# MAIN.net
KiCad netlist of a schematic drawn in Altium Designer
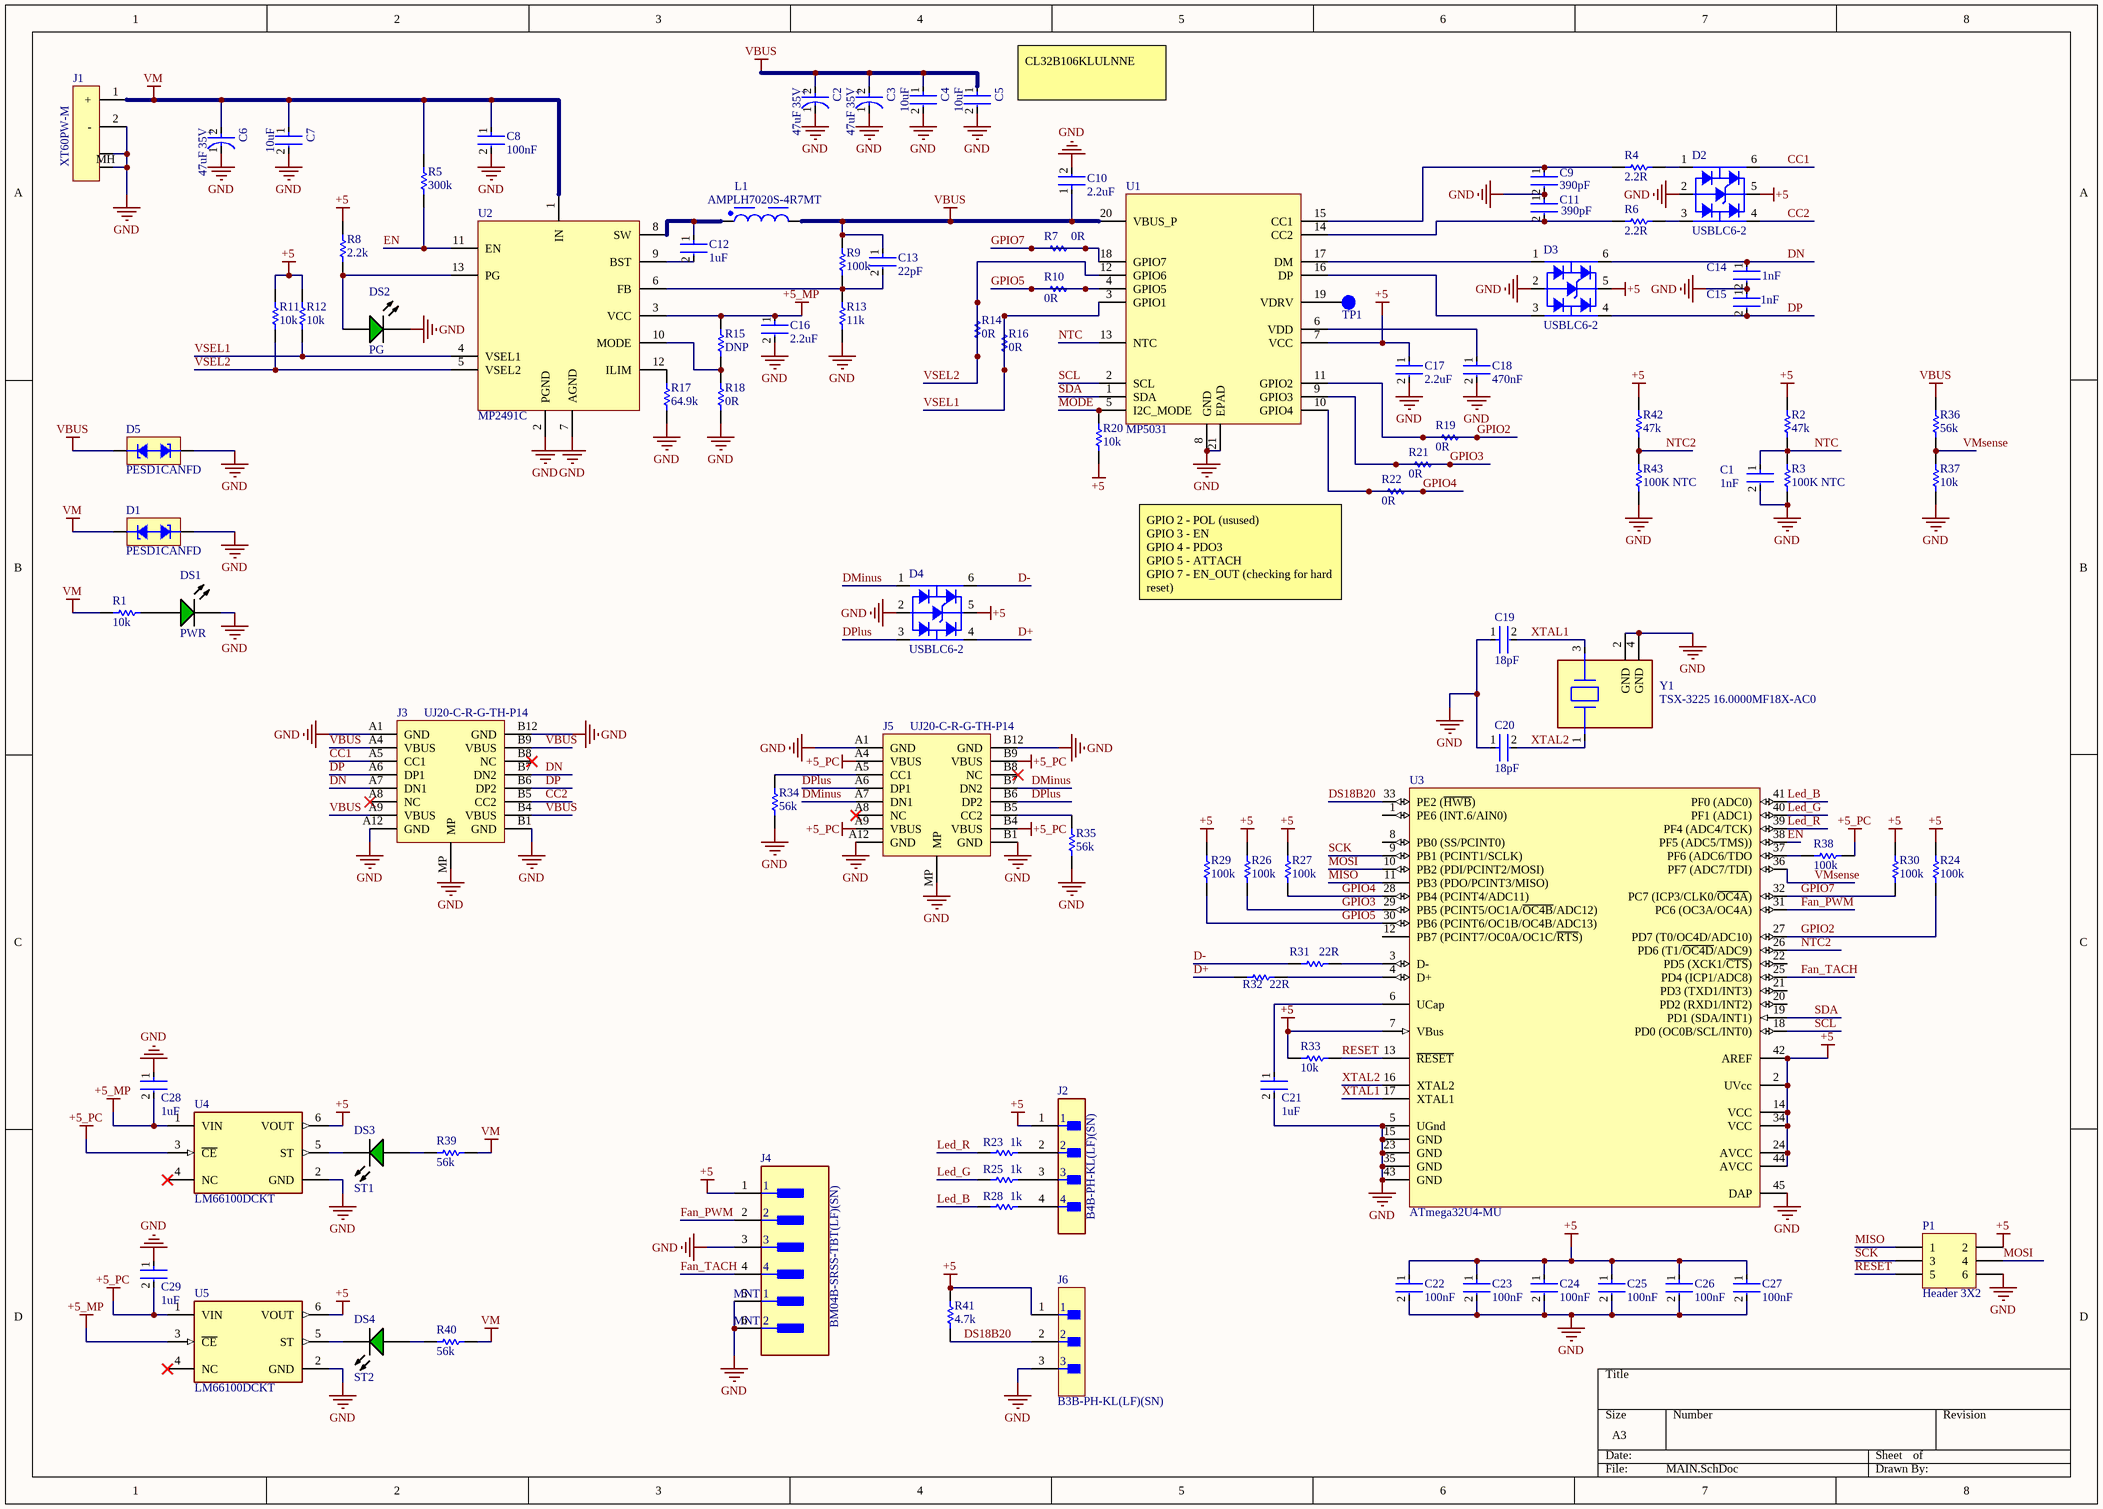
[diagram p0: MAIN.SchDoc]

(export (version "E")
  (design (tool "Eeschema 10.0.6"))
  (components
    (comp (ref "C1")
      (value "1nF")
      (footprint "FP-0603-L_1_6_0_15-W_0_81-IPC_B")
      (description "General Purpose Ceramic Capacitor, 0603, 1nF, 10%, X7R, 15%, 50V")
      (fields (field (name "VOLTAGE") "50V") (field (name "TOLERANCE") "10%"))
      (libsource (lib "Altium Content Vault") (part "02cd4be3c70576c341d710602a673aa"))
    )
    (comp (ref "C2")
      (value "47uF 35V")
      (footprint "FP-T491X476K035AT-MFG")
      (description "CAP TANT 47UF 10% 35V 2917")
      (fields (field (name "TOLERANCE") "10%") (field (name "VOLTAGE") "35V"))
      (libsource (lib "Altium Content Vault") (part "203bc49f2ac43e59fd269a8c329ed05"))
    )
    (comp (ref "C3")
      (value "47uF 35V")
      (footprint "FP-T491X476K035AT-MFG")
      (description "CAP TANT 47UF 10% 35V 2917")
      (fields (field (name "TOLERANCE") "10%") (field (name "VOLTAGE") "35V"))
      (libsource (lib "Altium Content Vault") (part "203bc49f2ac43e59fd269a8c329ed05"))
    )
    (comp (ref "C4")
      (value "10uF")
      (footprint "FP-C1210C106M6PACTU-MFG")
      (description "CAP CER 10UF 35V X5R 1210")
      (fields (field (name "VOLTAGE") "35V") (field (name "TOLERANCE") "20%"))
      (libsource (lib "Altium Content Vault") (part "02cd4be3c70576c341d710602a673aa"))
    )
    (comp (ref "C5")
      (value "10uF")
      (footprint "FP-C1210C106M6PACTU-MFG")
      (description "CAP CER 10UF 35V X5R 1210")
      (fields (field (name "VOLTAGE") "35V") (field (name "TOLERANCE") "20%"))
      (libsource (lib "Altium Content Vault") (part "02cd4be3c70576c341d710602a673aa"))
    )
    (comp (ref "C6")
      (value "47uF 35V")
      (footprint "FP-T491X476K035AT-MFG")
      (description "CAP TANT 47UF 10% 35V 2917")
      (fields (field (name "TOLERANCE") "10%") (field (name "VOLTAGE") "35V"))
      (libsource (lib "Altium Content Vault") (part "203bc49f2ac43e59fd269a8c329ed05"))
    )
    (comp (ref "C7")
      (value "10uF")
      (footprint "FP-C1210C106M6PACTU-MFG")
      (description "CAP CER 10UF 35V X5R 1210")
      (fields (field (name "VOLTAGE") "35V") (field (name "TOLERANCE") "20%"))
      (libsource (lib "Altium Content Vault") (part "02cd4be3c70576c341d710602a673aa"))
    )
    (comp (ref "C8")
      (value "100nF")
      (footprint "FP-0603-L_1_6_0_1-W_0_8_0-IPC_C")
      (description "None")
      (fields (field (name "TOLERANCE") "10%"))
      (libsource (lib "Altium Content Vault") (part "02cd4be3c70576c341d710602a673aa"))
    )
    (comp (ref "C9")
      (value "390pF")
      (footprint "FP-C0603C-CF-IPC_B")
      (description "CAP CER 390PF 50V C0G/NP0 0603")
      (fields
        (field (name "MANUFACTURER") "KEMET")
        (field (name "MANUFACTURER PART NUMBER") "C0603C391J5GACTU")
      )
      (libsource (lib "Altium Content Vault") (part "b4654b650e69147ec39a6b967a45e02"))
    )
    (comp (ref "C10")
      (value "2.2uF")
      (footprint "FP-GRM188-0_1-e0_2_0_5-IPC_B")
      (description "Chip Multilayer Ceramic Capacitors for General Purpose, 0603, 2.2uF, X7R, 15%, 10%, 10V")
      (fields (field (name "VOLTAGE") "10V") (field (name "TOLERANCE") "10%"))
      (libsource (lib "Altium Content Vault") (part "11868f565c42a9108669ba33697ecf6"))
    )
    (comp (ref "C11")
      (value "390pF")
      (footprint "FP-C0603C-CF-IPC_B")
      (description "CAP CER 390PF 50V C0G/NP0 0603")
      (fields
        (field (name "MANUFACTURER") "KEMET")
        (field (name "MANUFACTURER PART NUMBER") "C0603C391J5GACTU")
      )
      (libsource (lib "Altium Content Vault") (part "b4654b650e69147ec39a6b967a45e02"))
    )
    (comp (ref "C12")
      (value "1uF")
      (footprint "FP-0603-L_1_6_0_15-W_0_81-IPC_B")
      (description "General Purpose Ceramic Capacitor, 0603, 1uF, 10%, X5R, 15%, 16V")
      (fields (field (name "VOLTAGE") "16V") (field (name "TOLERANCE") "10%"))
      (libsource (lib "Altium Content Vault") (part "02cd4be3c70576c341d710602a673aa"))
    )
    (comp (ref "C13")
      (value "22pF")
      (footprint "FP-C0603C-CF-MFG")
      (description "Cap Ceramic 22pF 50V C0G 5% SMD 0603 125°C Paper T/R")
      (fields (field (name "MANUFACTURER PART NUMBER") "C0603C220J5GACTU") (field (name "TOLERANCE") "0.05"))
      (libsource (lib "Altium Content Vault") (part "b4654b650e69147ec39a6b967a45e02"))
    )
    (comp (ref "C14")
      (value "1nF")
      (footprint "FP-0603-L_1_6_0_15-W_0_81-IPC_B")
      (description "General Purpose Ceramic Capacitor, 0603, 1nF, 10%, X7R, 15%, 50V")
      (fields (field (name "VOLTAGE") "50V") (field (name "TOLERANCE") "10%"))
      (libsource (lib "Altium Content Vault") (part "02cd4be3c70576c341d710602a673aa"))
    )
    (comp (ref "C15")
      (value "1nF")
      (footprint "FP-0603-L_1_6_0_15-W_0_81-IPC_B")
      (description "General Purpose Ceramic Capacitor, 0603, 1nF, 10%, X7R, 15%, 50V")
      (fields (field (name "VOLTAGE") "50V") (field (name "TOLERANCE") "10%"))
      (libsource (lib "Altium Content Vault") (part "02cd4be3c70576c341d710602a673aa"))
    )
    (comp (ref "C16")
      (value "2.2uF")
      (footprint "FP-GRM188-0_1-e0_2_0_5-IPC_B")
      (description "Chip Multilayer Ceramic Capacitors for General Purpose, 0603, 2.2uF, X7R, 15%, 10%, 10V")
      (fields (field (name "VOLTAGE") "10V") (field (name "TOLERANCE") "10%"))
      (libsource (lib "Altium Content Vault") (part "11868f565c42a9108669ba33697ecf6"))
    )
    (comp (ref "C17")
      (value "2.2uF")
      (footprint "FP-GRM188-0_1-e0_2_0_5-IPC_B")
      (description "Chip Multilayer Ceramic Capacitors for General Purpose, 0603, 2.2uF, X7R, 15%, 10%, 10V")
      (fields (field (name "VOLTAGE") "10V") (field (name "TOLERANCE") "10%"))
      (libsource (lib "Altium Content Vault") (part "11868f565c42a9108669ba33697ecf6"))
    )
    (comp (ref "C18")
      (value "470nF")
      (footprint "FP-C0603C-CF-IPC_B")
      (description "CAP CER 0.47UF 16V X7R 0603")
      (fields (field (name "TOLERANCE") "0.1") (field (name "MANUFACTURER PART NUMBER") "C0603C474K4RACTU"))
      (libsource (lib "Altium Content Vault") (part "b4654b650e69147ec39a6b967a45e02"))
    )
    (comp (ref "C19")
      (value "18pF")
      (footprint "FP-C0603C-CF-MFG")
      (description "C0603 18 pF X8R 30ppm/°C 10.00% 16 V")
      (fields
        (field (name "TOLERANCE") "0.1")
        (field (name "OCTOPART") "https://octopart.com/c0603c180k4hactu-kemet-88725221")
      )
      (libsource (lib "Altium Content Vault") (part "b4654b650e69147ec39a6b967a45e02"))
    )
    (comp (ref "C20")
      (value "18pF")
      (footprint "FP-C0603C-CF-MFG")
      (description "C0603 18 pF X8R 30ppm/°C 10.00% 16 V")
      (fields
        (field (name "TOLERANCE") "0.1")
        (field (name "OCTOPART") "https://octopart.com/c0603c180k4hactu-kemet-88725221")
      )
      (libsource (lib "Altium Content Vault") (part "b4654b650e69147ec39a6b967a45e02"))
    )
    (comp (ref "C21")
      (value "1uF")
      (footprint "FP-0603-L_1_6_0_15-W_0_81-MFG")
      (description "General Purpose Ceramic Capacitor, 0603, 1uF, 10%, X5R, 15%, 16V")
      (fields (field (name "VOLTAGE") "16V") (field (name "TOLERANCE") "10%"))
      (libsource (lib "Altium Content Vault") (part "02cd4be3c70576c341d710602a673aa"))
    )
    (comp (ref "C22")
      (value "100nF")
      (footprint "FP-0603-L_1_6_0_1-W_0_8_0-MFG")
      (description "None")
      (fields (field (name "TOLERANCE") "10%"))
      (libsource (lib "Altium Content Vault") (part "02cd4be3c70576c341d710602a673aa"))
    )
    (comp (ref "C23")
      (value "100nF")
      (footprint "FP-0603-L_1_6_0_1-W_0_8_0-MFG")
      (description "None")
      (fields (field (name "TOLERANCE") "10%"))
      (libsource (lib "Altium Content Vault") (part "02cd4be3c70576c341d710602a673aa"))
    )
    (comp (ref "C24")
      (value "100nF")
      (footprint "FP-0603-L_1_6_0_1-W_0_8_0-MFG")
      (description "None")
      (fields (field (name "TOLERANCE") "10%"))
      (libsource (lib "Altium Content Vault") (part "02cd4be3c70576c341d710602a673aa"))
    )
    (comp (ref "C25")
      (value "100nF")
      (footprint "FP-0603-L_1_6_0_1-W_0_8_0-MFG")
      (description "None")
      (fields (field (name "TOLERANCE") "10%"))
      (libsource (lib "Altium Content Vault") (part "02cd4be3c70576c341d710602a673aa"))
    )
    (comp (ref "C26")
      (value "100nF")
      (footprint "FP-0603-L_1_6_0_1-W_0_8_0-MFG")
      (description "None")
      (fields (field (name "TOLERANCE") "10%"))
      (libsource (lib "Altium Content Vault") (part "02cd4be3c70576c341d710602a673aa"))
    )
    (comp (ref "C27")
      (value "100nF")
      (footprint "FP-0603-L_1_6_0_1-W_0_8_0-MFG")
      (description "None")
      (fields (field (name "TOLERANCE") "10%"))
      (libsource (lib "Altium Content Vault") (part "02cd4be3c70576c341d710602a673aa"))
    )
    (comp (ref "C28")
      (value "1uF")
      (footprint "FP-0603-L_1_6_0_15-W_0_81-IPC_B")
      (description "General Purpose Ceramic Capacitor, 0603, 1uF, 10%, X5R, 15%, 16V")
      (fields (field (name "VOLTAGE") "16V") (field (name "TOLERANCE") "10%"))
      (libsource (lib "Altium Content Vault") (part "02cd4be3c70576c341d710602a673aa"))
    )
    (comp (ref "C29")
      (value "1uF")
      (footprint "FP-0603-L_1_6_0_15-W_0_81-IPC_B")
      (description "General Purpose Ceramic Capacitor, 0603, 1uF, 10%, X5R, 15%, 16V")
      (fields (field (name "VOLTAGE") "16V") (field (name "TOLERANCE") "10%"))
      (libsource (lib "Altium Content Vault") (part "02cd4be3c70576c341d710602a673aa"))
    )
    (comp (ref "D1")
      (value "PESD1CANFD")
      (footprint "DIOM1006X05N")
      (description "Extremely low clamping bidirectional ESD protection diode")
      (libsource (lib "PC_PSU") (part "PESD1CANFD"))
    )
    (comp (ref "D2")
      (value "USBLC6-2")
      (footprint "SOT95P280X145-6N")
      (description "Very low capacitance ESD protection")
      (libsource (lib "PC_PSU") (part "USBLC6-2"))
    )
    (comp (ref "D3")
      (value "USBLC6-2")
      (footprint "SOT95P280X145-6N")
      (description "Very low capacitance ESD protection")
      (libsource (lib "PC_PSU") (part "USBLC6-2"))
    )
    (comp (ref "D4")
      (value "USBLC6-2")
      (footprint "SOT95P280X145-6N")
      (description "Very low capacitance ESD protection")
      (libsource (lib "PC_PSU") (part "USBLC6-2"))
    )
    (comp (ref "D5")
      (value "PESD1CANFD")
      (footprint "DIOM1006X05N")
      (description "Extremely low clamping bidirectional ESD protection diode")
      (libsource (lib "PC_PSU") (part "PESD1CANFD"))
    )
    (comp (ref "DS1")
      (value "PWR")
      (footprint "AVAG-HSMX-C170_V")
      (description "Chip LED, Green, 2.2 V, -40 to 85 degC, 2-Pin SMD, Pb-Free, Tape and Reel")
      (fields (field (name "MANUFACTURER") "Avago"))
      (libsource (lib "Altium Content Vault") (part "LED_GREEN_A1K2-2"))
    )
    (comp (ref "DS2")
      (value "PG")
      (footprint "AVAG-HSMX-C170_V")
      (description "Chip LED, Green, 2.2 V, -40 to 85 degC, 2-Pin SMD, Pb-Free, Tape and Reel")
      (fields (field (name "MANUFACTURER") "Avago"))
      (libsource (lib "Altium Content Vault") (part "LED_GREEN_A1K2-2"))
    )
    (comp (ref "DS3")
      (value "ST1")
      (footprint "AVAG-HSMX-C170_V")
      (description "Chip LED, Green, 2.2 V, -40 to 85 degC, 2-Pin SMD, Pb-Free, Tape and Reel")
      (fields (field (name "MANUFACTURER") "Avago"))
      (libsource (lib "Altium Content Vault") (part "LED_GREEN_A1K2-2"))
    )
    (comp (ref "DS4")
      (value "ST2")
      (footprint "AVAG-HSMX-C170_V")
      (description "Chip LED, Green, 2.2 V, -40 to 85 degC, 2-Pin SMD, Pb-Free, Tape and Reel")
      (fields (field (name "MANUFACTURER") "Avago"))
      (libsource (lib "Altium Content Vault") (part "LED_GREEN_A1K2-2"))
    )
    (comp (ref "J1")
      (value "XT60PW-M")
      (footprint "XT60PW-M")
      (description "Connector: DC supply; socket; XT60; male; PIN: 2; on PCBs; THT; 30A")
      (libsource (lib "PC_PSU") (part "XT60PW-M"))
    )
    (comp (ref "J2")
      (value "B4B-PH-KL(LF)(SN)")
      (footprint "FP-B4B-PH-KL_LF_SN-MFG")
      (description "CONN HEADER VERT 4POS 2MM")
      (libsource (lib "Altium Content Vault") (part "299a8cea1bdcbc3624fe62c390fa72c"))
    )
    (comp (ref "J3")
      (value "UJ20-C-R-G-TH-P14")
      (footprint "UJ20-C-R-G-TH-P14")
      (libsource (lib "MPS") (part "USB C"))
    )
    (comp (ref "J4")
      (value "BM04B-SRSS-TBT(LF)(SN)")
      (footprint "FP-BM04B-SRSS-TBT_LF_SN-MFG")
      (description "CONN HEADER SMD 4POS 1MM")
      (libsource (lib "Altium Content Vault") (part "8e3688c4b118bffc0dd9b7401e414ba"))
    )
    (comp (ref "J5")
      (value "UJ20-C-R-G-TH-P14")
      (footprint "UJ20-C-R-G-TH-P14")
      (libsource (lib "MPS") (part "USB C"))
    )
    (comp (ref "J6")
      (value "B3B-PH-KL(LF)(SN)")
      (footprint "FP-B3B-PH-KL_LF_SN-MFG")
      (libsource (lib "Altium Content Vault") (part "0d3f023dd272f625e17a2be33dea85f"))
    )
    (comp (ref "L1")
      (value "AMPLH7020S-4R7MT")
      (footprint "INDP7366X20N")
      (description "FIXED IND 4.7UH 5.5A 45.6MOHM SM")
      (libsource (lib "AMPLH7020S") (part "AMPLH7020S-4R7MT"))
    )
    (comp (ref "P1")
      (value "Header 3X2")
      (footprint "HDR2X3")
      (description "Header, 3-Pin, Dual row")
      (fields (field (name "PUBLISHER") "Altium Limited"))
      (libsource (lib "Miscellaneous Connectors") (part "Header 3X2"))
    )
    (comp (ref "R1")
      (value "10k")
      (footprint "RESC1609X55X30NL15T15")
      (description "Chip Resistor, 10 KOhm, +/- 1%, 0.1 W, -55 to 155 degC, 0603 (1608 Metric), RoHS, Tape and Reel")
      (fields (field (name "TOLERANCE") "1%") (field (name "MANUFACTURER") "Panasonic"))
      (libsource (lib "Altium Content Vault") (part "RES-2"))
    )
    (comp (ref "R2")
      (value "47k")
      (footprint "RESC1608X55X30NL15T15")
      (description "Chip Resistor, 47 KOhm, +/- 1%, 0.1 W, -55 to 155 degC, 0603 (1608 Metric), RoHS, Tape and Reel")
      (libsource (lib "Altium Content Vault") (part "RES-2"))
    )
    (comp (ref "R3")
      (value "100K NTC")
      (footprint "RESC0603(1608)_N")
      (description "100K 0.1W 5% 0603 (1608 Metric)  SMD")
      (fields (field (name "TOLERANCE") "5 %") (field (name "POWER") "0.1 W"))
      (libsource (lib "Altium Content Vault") (part "RES"))
    )
    (comp (ref "R4")
      (value "2.2R")
      (footprint "RESC1609X50X30NL10T20")
      (fields (field (name "MANUFACTURER") "Vishay Dale") (field (name "PART NUMBER") "CRCW06032R20FKEA"))
      (libsource (lib "Altium Content Vault") (part "RES"))
    )
    (comp (ref "R5")
      (value "300k")
      (footprint "RESC1609X50X30NL10T20")
      (fields (field (name "MANUFACTURER") "Vishay Dale") (field (name "PART NUMBER") "CRCW0603300KFKEA"))
      (libsource (lib "Altium Content Vault") (part "RES"))
    )
    (comp (ref "R6")
      (value "2.2R")
      (footprint "RESC1609X50X30NL10T20")
      (fields (field (name "MANUFACTURER") "Vishay Dale") (field (name "PART NUMBER") "CRCW06032R20FKEA"))
      (libsource (lib "Altium Content Vault") (part "RES"))
    )
    (comp (ref "R7")
      (value "0R")
      (footprint "RESC1608X55X25NL10T15")
      (description "Chip Resistor, 0 Ohm, +/- 5%, 0.1 W, -55 to 155 degC, 0603 (1608 Metric), RoHS, Tape and Reel")
      (fields (field (name "TOLERANCE") "5%") (field (name "MANUFACTURER") "Yageo"))
      (libsource (lib "Altium Content Vault") (part "RES-2"))
    )
    (comp (ref "R8")
      (value "2.2k")
      (footprint "RESC1608X50X30NL20T20")
      (fields (field (name "PART NUMBER") "RR0816P-223-B-T5") (field (name "MANUFACTURER") "Susumu"))
      (libsource (lib "Altium Content Vault") (part "RES"))
    )
    (comp (ref "R9")
      (value "100k")
      (footprint "RESC1608X55X30LL15T15")
      (fields (field (name "PART NUMBER") "ERJ-3EKF1003V") (field (name "MANUFACTURER") "Panasonic"))
      (libsource (lib "Altium Content Vault") (part "RES"))
    )
    (comp (ref "R10")
      (value "0R")
      (footprint "RESC1608X55X25NL10T15")
      (description "Chip Resistor, 0 Ohm, +/- 5%, 0.1 W, -55 to 155 degC, 0603 (1608 Metric), RoHS, Tape and Reel")
      (fields (field (name "TOLERANCE") "5%") (field (name "MANUFACTURER") "Yageo"))
      (libsource (lib "Altium Content Vault") (part "RES-2"))
    )
    (comp (ref "R11")
      (value "10k")
      (footprint "RESC1609X55X30NL15T15")
      (description "Chip Resistor, 10 KOhm, +/- 1%, 0.1 W, -55 to 155 degC, 0603 (1608 Metric), RoHS, Tape and Reel")
      (fields (field (name "TOLERANCE") "1%") (field (name "MANUFACTURER") "Panasonic"))
      (libsource (lib "Altium Content Vault") (part "RES-2"))
    )
    (comp (ref "R12")
      (value "10k")
      (footprint "RESC1609X55X30NL15T15")
      (description "Chip Resistor, 10 KOhm, +/- 1%, 0.1 W, -55 to 155 degC, 0603 (1608 Metric), RoHS, Tape and Reel")
      (fields (field (name "TOLERANCE") "1%") (field (name "MANUFACTURER") "Panasonic"))
      (libsource (lib "Altium Content Vault") (part "RES-2"))
    )
    (comp (ref "R13")
      (value "11k")
      (footprint "RESC1609X50X30LL10T20")
      (fields (field (name "PART NUMBER") "CRCW060311K0FKEA") (field (name "MANUFACTURER") "Vishay Dale"))
      (libsource (lib "Altium Content Vault") (part "RES"))
    )
    (comp (ref "R14")
      (value "0R")
      (footprint "RESC1608X55X25NL10T15")
      (description "Chip Resistor, 0 Ohm, +/- 5%, 0.1 W, -55 to 155 degC, 0603 (1608 Metric), RoHS, Tape and Reel")
      (fields (field (name "TOLERANCE") "5%") (field (name "MANUFACTURER") "Yageo"))
      (libsource (lib "Altium Content Vault") (part "RES-2"))
    )
    (comp (ref "R15")
      (value "DNP")
      (footprint "RESC1608X55X25NL10T15")
      (description "Chip Resistor, 0 Ohm, +/- 5%, 0.1 W, -55 to 155 degC, 0603 (1608 Metric), RoHS, Tape and Reel")
      (fields (field (name "TOLERANCE") "5%") (field (name "MANUFACTURER") "Yageo"))
      (libsource (lib "Altium Content Vault") (part "RES-2"))
    )
    (comp (ref "R16")
      (value "0R")
      (footprint "RESC1608X55X25NL10T15")
      (description "Chip Resistor, 0 Ohm, +/- 5%, 0.1 W, -55 to 155 degC, 0603 (1608 Metric), RoHS, Tape and Reel")
      (fields (field (name "TOLERANCE") "5%") (field (name "MANUFACTURER") "Yageo"))
      (libsource (lib "Altium Content Vault") (part "RES-2"))
    )
    (comp (ref "R17")
      (value "64.9k")
      (footprint "RESC1608X55X30NL15T15")
      (fields (field (name "PART NUMBER") "ERJ-3EKF6492V") (field (name "MANUFACTURER") "Panasonic"))
      (libsource (lib "Altium Content Vault") (part "RES"))
    )
    (comp (ref "R18")
      (value "0R")
      (footprint "RESC1608X55X25NL10T15")
      (description "Chip Resistor, 0 Ohm, +/- 5%, 0.1 W, -55 to 155 degC, 0603 (1608 Metric), RoHS, Tape and Reel")
      (fields (field (name "TOLERANCE") "5%") (field (name "MANUFACTURER") "Yageo"))
      (libsource (lib "Altium Content Vault") (part "RES-2"))
    )
    (comp (ref "R19")
      (value "0R")
      (footprint "RESC1608X55X25NL10T15")
      (description "Chip Resistor, 0 Ohm, +/- 5%, 0.1 W, -55 to 155 degC, 0603 (1608 Metric), RoHS, Tape and Reel")
      (fields (field (name "TOLERANCE") "5%") (field (name "MANUFACTURER") "Yageo"))
      (libsource (lib "Altium Content Vault") (part "RES-2"))
    )
    (comp (ref "R20")
      (value "10k")
      (footprint "RESC1609X55X30NL15T15")
      (description "Chip Resistor, 10 KOhm, +/- 1%, 0.1 W, -55 to 155 degC, 0603 (1608 Metric), RoHS, Tape and Reel")
      (fields (field (name "TOLERANCE") "1%") (field (name "MANUFACTURER") "Panasonic"))
      (libsource (lib "Altium Content Vault") (part "RES-2"))
    )
    (comp (ref "R21")
      (value "0R")
      (footprint "RESC1608X55X25NL10T15")
      (description "Chip Resistor, 0 Ohm, +/- 5%, 0.1 W, -55 to 155 degC, 0603 (1608 Metric), RoHS, Tape and Reel")
      (fields (field (name "TOLERANCE") "5%") (field (name "MANUFACTURER") "Yageo"))
      (libsource (lib "Altium Content Vault") (part "RES-2"))
    )
    (comp (ref "R22")
      (value "0R")
      (footprint "RESC1608X55X25NL10T15")
      (description "Chip Resistor, 0 Ohm, +/- 5%, 0.1 W, -55 to 155 degC, 0603 (1608 Metric), RoHS, Tape and Reel")
      (fields (field (name "TOLERANCE") "5%") (field (name "MANUFACTURER") "Yageo"))
      (libsource (lib "Altium Content Vault") (part "RES-2"))
    )
    (comp (ref "R23")
      (value "1k")
      (footprint "RESC1608X55X25NL10T15")
      (fields (field (name "PART NUMBER") "RT0603BRE071KL") (field (name "MANUFACTURER") "Yageo"))
      (libsource (lib "Altium Content Vault") (part "RES"))
    )
    (comp (ref "R24")
      (value "100k")
      (footprint "RESC1608X55X30NL15T15")
      (fields (field (name "PART NUMBER") "ERJ-3EKF1003V") (field (name "MANUFACTURER") "Panasonic"))
      (libsource (lib "Altium Content Vault") (part "RES"))
    )
    (comp (ref "R25")
      (value "1k")
      (footprint "RESC1608X55X25NL10T15")
      (fields (field (name "PART NUMBER") "RT0603BRE071KL") (field (name "MANUFACTURER") "Yageo"))
      (libsource (lib "Altium Content Vault") (part "RES"))
    )
    (comp (ref "R26")
      (value "100k")
      (footprint "RESC1608X55X30NL15T15")
      (fields (field (name "PART NUMBER") "ERJ-3EKF1003V") (field (name "MANUFACTURER") "Panasonic"))
      (libsource (lib "Altium Content Vault") (part "RES"))
    )
    (comp (ref "R27")
      (value "100k")
      (footprint "RESC1608X55X30NL15T15")
      (fields (field (name "PART NUMBER") "ERJ-3EKF1003V") (field (name "MANUFACTURER") "Panasonic"))
      (libsource (lib "Altium Content Vault") (part "RES"))
    )
    (comp (ref "R28")
      (value "1k")
      (footprint "RESC1608X55X25NL10T15")
      (fields (field (name "PART NUMBER") "RT0603BRE071KL") (field (name "MANUFACTURER") "Yageo"))
      (libsource (lib "Altium Content Vault") (part "RES"))
    )
    (comp (ref "R29")
      (value "100k")
      (footprint "RESC1608X55X30NL15T15")
      (fields (field (name "PART NUMBER") "ERJ-3EKF1003V") (field (name "MANUFACTURER") "Panasonic"))
      (libsource (lib "Altium Content Vault") (part "RES"))
    )
    (comp (ref "R30")
      (value "100k")
      (footprint "RESC1608X55X30NL15T15")
      (fields (field (name "PART NUMBER") "ERJ-3EKF1003V") (field (name "MANUFACTURER") "Panasonic"))
      (libsource (lib "Altium Content Vault") (part "RES"))
    )
    (comp (ref "R31")
      (value "22R")
      (footprint "RESC1608X55X30NL15T15")
      (description "Chip Resistor, 22 Ohm, +/- 1%, 0.1 W, -55 to 155 degC, 0603 (1608 Metric), RoHS, Tape and Reel")
      (libsource (lib "Altium Content Vault") (part "RES-2"))
    )
    (comp (ref "R32")
      (value "22R")
      (footprint "RESC1608X55X30NL15T15")
      (description "Chip Resistor, 22 Ohm, +/- 1%, 0.1 W, -55 to 155 degC, 0603 (1608 Metric), RoHS, Tape and Reel")
      (libsource (lib "Altium Content Vault") (part "RES-2"))
    )
    (comp (ref "R33")
      (value "10k")
      (footprint "RESC1609X55X30NL15T15")
      (description "Chip Resistor, 10 KOhm, +/- 1%, 0.1 W, -55 to 155 degC, 0603 (1608 Metric), RoHS, Tape and Reel")
      (fields (field (name "TOLERANCE") "1%") (field (name "MANUFACTURER") "Panasonic"))
      (libsource (lib "Altium Content Vault") (part "RES-2"))
    )
    (comp (ref "R34")
      (value "56k")
      (footprint "RESC0603(1608)_N")
      (description "56K 0.1W 5% 0603 (1608 Metric)  SMD")
      (fields (field (name "TOLERANCE") "5 %") (field (name "POWER") "0.1 W"))
      (libsource (lib "Altium Content Vault") (part "RES"))
    )
    (comp (ref "R35")
      (value "56k")
      (footprint "RESC0603(1608)_N")
      (description "56K 0.1W 5% 0603 (1608 Metric)  SMD")
      (fields (field (name "TOLERANCE") "5 %") (field (name "POWER") "0.1 W"))
      (libsource (lib "Altium Content Vault") (part "RES"))
    )
    (comp (ref "R36")
      (value "56k")
      (footprint "RESC0603(1608)_N")
      (description "56K 0.1W 5% 0603 (1608 Metric)  SMD")
      (fields (field (name "TOLERANCE") "5 %") (field (name "POWER") "0.1 W"))
      (libsource (lib "Altium Content Vault") (part "RES"))
    )
    (comp (ref "R37")
      (value "10k")
      (footprint "RESC1609X55X30NL15T15")
      (description "Chip Resistor, 10 KOhm, +/- 1%, 0.1 W, -55 to 155 degC, 0603 (1608 Metric), RoHS, Tape and Reel")
      (fields (field (name "TOLERANCE") "1%") (field (name "MANUFACTURER") "Panasonic"))
      (libsource (lib "Altium Content Vault") (part "RES-2"))
    )
    (comp (ref "R38")
      (value "100k")
      (footprint "RESC1608X55X30NL15T15")
      (fields (field (name "PART NUMBER") "ERJ-3EKF1003V") (field (name "MANUFACTURER") "Panasonic"))
      (libsource (lib "Altium Content Vault") (part "RES"))
    )
    (comp (ref "R39")
      (value "56k")
      (footprint "RESC0603(1608)_N")
      (description "56K 0.1W 5% 0603 (1608 Metric)  SMD")
      (fields (field (name "TOLERANCE") "5 %") (field (name "POWER") "0.1 W"))
      (libsource (lib "Altium Content Vault") (part "RES"))
    )
    (comp (ref "R40")
      (value "56k")
      (footprint "RESC0603(1608)_N")
      (description "56K 0.1W 5% 0603 (1608 Metric)  SMD")
      (fields (field (name "TOLERANCE") "5 %") (field (name "POWER") "0.1 W"))
      (libsource (lib "Altium Content Vault") (part "RES"))
    )
    (comp (ref "R41")
      (value "4.7k")
      (footprint "RESC1608X55X30NL15T15")
      (fields (field (name "TOLERANCE") "5%"))
      (libsource (lib "Altium Content Vault") (part "RES-2"))
    )
    (comp (ref "R42")
      (value "47k")
      (footprint "RESC1608X55X30NL15T15")
      (description "Chip Resistor, 47 KOhm, +/- 1%, 0.1 W, -55 to 155 degC, 0603 (1608 Metric), RoHS, Tape and Reel")
      (libsource (lib "Altium Content Vault") (part "RES-2"))
    )
    (comp (ref "R43")
      (value "100K NTC")
      (footprint "RESC0603(1608)_N")
      (description "100K 0.1W 5% 0603 (1608 Metric)  SMD")
      (fields (field (name "TOLERANCE") "5 %") (field (name "POWER") "0.1 W"))
      (libsource (lib "Altium Content Vault") (part "RES"))
    )
    (comp (ref "TP1")
      (value "TESTPOINT")
      (footprint "TESTPOINT_0.6")
      (libsource (lib "MPS") (part "TESTPOINT"))
    )
    (comp (ref "U1") (value "MP5031") (footprint "QFN-20-MP5031") (libsource (lib "MPS") (part "MP5031")))
    (comp (ref "U2") (value "MP2491C") (footprint "QFN-13-MPS2491C") (libsource (lib "MPS") (part "MP2491C")))
    (comp (ref "U3")
      (value "ATmega32U4-MU")
      (footprint "44PW_M")
      (libsource (lib "Altium Content Vault") (part "MC-8B-ATM16U4-SQ45"))
    )
    (comp (ref "U4")
      (value "LM66100DCKT")
      (footprint "FP-DCK0006A-MFG")
      (description "IC OR CTRLR IDEAL DIODE SC70-6")
      (libsource (lib "Altium Content Vault") (part "3595dc506fef48fc1df3095330a4feb"))
    )
    (comp (ref "U5")
      (value "LM66100DCKT")
      (footprint "FP-DCK0006A-MFG")
      (description "IC OR CTRLR IDEAL DIODE SC70-6")
      (libsource (lib "Altium Content Vault") (part "3595dc506fef48fc1df3095330a4feb"))
    )
    (comp (ref "Y1")
      (value "TSX-3225 16.0000MF18X-AC0")
      (footprint "FP-TSX-3225-MFG")
      (description "CRYSTAL 16.00 MHZ 9PF SMD")
      (fields
        (field (name "OCTOPART") "https://octopart.com/tsx-3225+16.0000mf18x-ac0-epson-58756552")
        (field (name "MANUFACTURER") "EPSON")
      )
      (libsource (lib "Altium Content Vault") (part "a9e65936d6f6a8cd8abf4b50f2664b9"))
    )
  )
  (nets
    (net (code "1") (name "+5") (class "Default")
      (node (ref "C17") (pin "1") (pinfunction "1_1") (pintype "passive"))
      (node (ref "C22") (pin "1") (pinfunction "1_1") (pintype "passive"))
      (node (ref "C23") (pin "1") (pinfunction "1_1") (pintype "passive"))
      (node (ref "C24") (pin "1") (pinfunction "1_1") (pintype "passive"))
      (node (ref "C25") (pin "1") (pinfunction "1_1") (pintype "passive"))
      (node (ref "C26") (pin "1") (pinfunction "1_1") (pintype "passive"))
      (node (ref "C27") (pin "1") (pinfunction "1_1") (pintype "passive"))
      (node (ref "D2") (pin "5") (pinfunction "5_5") (pintype "passive"))
      (node (ref "D3") (pin "5") (pinfunction "5_5") (pintype "passive"))
      (node (ref "D4") (pin "5") (pinfunction "5_5") (pintype "passive"))
      (node (ref "J2") (pin "1") (pinfunction "1_1") (pintype "passive"))
      (node (ref "J4") (pin "1") (pinfunction "1_1") (pintype "passive"))
      (node (ref "J6") (pin "1") (pinfunction "1_1") (pintype "passive"))
      (node (ref "P1") (pin "2") (pinfunction "2_2") (pintype "passive"))
      (node (ref "R11") (pin "2") (pinfunction "2_2") (pintype "passive"))
      (node (ref "R12") (pin "2") (pinfunction "2_2") (pintype "passive"))
      (node (ref "R2") (pin "2") (pinfunction "2_2") (pintype "passive"))
      (node (ref "R20") (pin "1") (pinfunction "1_1") (pintype "passive"))
      (node (ref "R24") (pin "2") (pinfunction "2_2") (pintype "passive"))
      (node (ref "R26") (pin "2") (pinfunction "2_2") (pintype "passive"))
      (node (ref "R27") (pin "2") (pinfunction "2_2") (pintype "passive"))
      (node (ref "R29") (pin "2") (pinfunction "2_2") (pintype "passive"))
      (node (ref "R30") (pin "2") (pinfunction "2_2") (pintype "passive"))
      (node (ref "R33") (pin "2") (pinfunction "2_2") (pintype "passive"))
      (node (ref "R41") (pin "2") (pinfunction "2_2") (pintype "passive"))
      (node (ref "R42") (pin "2") (pinfunction "2_2") (pintype "passive"))
      (node (ref "R8") (pin "2") (pinfunction "2_2") (pintype "passive"))
      (node (ref "U1") (pin "7") (pinfunction "VCC_7") (pintype "passive"))
      (node (ref "U3") (pin "14") (pinfunction "VCC_14") (pintype "power_in"))
      (node (ref "U3") (pin "2") (pinfunction "UVcc_2") (pintype "power_in"))
      (node (ref "U3") (pin "24") (pinfunction "AVCC_24") (pintype "power_in"))
      (node (ref "U3") (pin "34") (pinfunction "VCC_34") (pintype "power_in"))
      (node (ref "U3") (pin "42") (pinfunction "AREF_42") (pintype "passive"))
      (node (ref "U3") (pin "44") (pinfunction "AVCC_44") (pintype "power_in"))
      (node (ref "U3") (pin "7") (pinfunction "VBus_7") (pintype "input"))
      (node (ref "U4") (pin "6") (pinfunction "VOUT_6") (pintype "output"))
      (node (ref "U5") (pin "6") (pinfunction "VOUT_6") (pintype "output"))
    )
    (net (code "2") (name "+5_MP") (class "Default")
      (node (ref "C16") (pin "1") (pinfunction "1_1") (pintype "passive"))
      (node (ref "C28") (pin "2") (pinfunction "2_2") (pintype "passive"))
      (node (ref "R15") (pin "2") (pinfunction "2_2") (pintype "passive"))
      (node (ref "U2") (pin "3") (pinfunction "VCC_3") (pintype "passive"))
      (node (ref "U4") (pin "1") (pinfunction "VIN_1") (pintype "power_in"))
      (node (ref "U5") (pin "3") (pinfunction "~{CE}_3") (pintype "input"))
    )
    (net (code "3") (name "+5_PC") (class "Default")
      (node (ref "C29") (pin "2") (pinfunction "2_2") (pintype "passive"))
      (node (ref "J5") (pin "A4") (pinfunction "VBUS_A4") (pintype "passive"))
      (node (ref "J5") (pin "A9") (pinfunction "VBUS_A9") (pintype "passive"))
      (node (ref "J5") (pin "B4") (pinfunction "VBUS_B4") (pintype "passive"))
      (node (ref "J5") (pin "B9") (pinfunction "VBUS_B9") (pintype "passive"))
      (node (ref "R38") (pin "1") (pinfunction "1_1") (pintype "passive"))
      (node (ref "U4") (pin "3") (pinfunction "~{CE}_3") (pintype "input"))
      (node (ref "U5") (pin "1") (pinfunction "VIN_1") (pintype "power_in"))
    )
    (net (code "4") (name "/CC1") (class "Default")
      (node (ref "D2") (pin "6") (pinfunction "6_6") (pintype "passive"))
      (node (ref "J3") (pin "A5") (pinfunction "CC1_A5") (pintype "passive"))
    )
    (net (code "5") (name "/CC2") (class "Default")
      (node (ref "D2") (pin "4") (pinfunction "4_4") (pintype "passive"))
      (node (ref "J3") (pin "B5") (pinfunction "CC2_B5") (pintype "passive"))
    )
    (net (code "6") (name "/D+") (class "Default")
      (node (ref "D4") (pin "4") (pinfunction "4_4") (pintype "passive"))
      (node (ref "R32") (pin "1") (pinfunction "1_1") (pintype "passive"))
    )
    (net (code "7") (name "/D-") (class "Default")
      (node (ref "D4") (pin "6") (pinfunction "6_6") (pintype "passive"))
      (node (ref "R31") (pin "1") (pinfunction "1_1") (pintype "passive"))
    )
    (net (code "8") (name "/DMinus") (class "Default")
      (node (ref "D4") (pin "1") (pinfunction "1_1") (pintype "passive"))
      (node (ref "J5") (pin "A7") (pinfunction "DN1_A7") (pintype "passive"))
      (node (ref "J5") (pin "B7") (pinfunction "DN2_B7") (pintype "passive"))
    )
    (net (code "9") (name "/DN") (class "Default")
      (node (ref "C14") (pin "1") (pinfunction "1_1") (pintype "passive"))
      (node (ref "D3") (pin "6") (pinfunction "6_6") (pintype "passive"))
      (node (ref "J3") (pin "A7") (pinfunction "DN1_A7") (pintype "passive"))
      (node (ref "J3") (pin "B7") (pinfunction "DN2_B7") (pintype "passive"))
    )
    (net (code "10") (name "/DP") (class "Default")
      (node (ref "C15") (pin "2") (pinfunction "2_2") (pintype "passive"))
      (node (ref "D3") (pin "4") (pinfunction "4_4") (pintype "passive"))
      (node (ref "J3") (pin "A6") (pinfunction "DP1_A6") (pintype "passive"))
      (node (ref "J3") (pin "B6") (pinfunction "DP2_B6") (pintype "passive"))
    )
    (net (code "11") (name "/DPlus") (class "Default")
      (node (ref "D4") (pin "3") (pinfunction "3_3") (pintype "passive"))
      (node (ref "J5") (pin "A6") (pinfunction "DP1_A6") (pintype "passive"))
      (node (ref "J5") (pin "B6") (pinfunction "DP2_B6") (pintype "passive"))
    )
    (net (code "12") (name "/DS18B20") (class "Default")
      (node (ref "J6") (pin "2") (pinfunction "2_2") (pintype "passive"))
      (node (ref "R41") (pin "1") (pinfunction "1_1") (pintype "passive"))
      (node (ref "U3") (pin "33") (pinfunction "PE2_(~{HWB})_33") (pintype "bidirectional"))
    )
    (net (code "13") (name "/EN") (class "Default")
      (node (ref "R5") (pin "1") (pinfunction "1_1") (pintype "passive"))
      (node (ref "U2") (pin "11") (pinfunction "EN_11") (pintype "passive"))
      (node (ref "U3") (pin "38") (pinfunction "PF5_(ADC5/TMS))_38") (pintype "bidirectional"))
    )
    (net (code "14") (name "/Fan_PWM") (class "Default")
      (node (ref "J4") (pin "2") (pinfunction "2_2") (pintype "passive"))
      (node (ref "U3") (pin "31") (pinfunction "PC6_(OC3A/OC4A)_31") (pintype "bidirectional"))
    )
    (net (code "15") (name "/Fan_TACH") (class "Default")
      (node (ref "J4") (pin "4") (pinfunction "4_4") (pintype "passive"))
      (node (ref "U3") (pin "25") (pinfunction "PD4_(ICP1/ADC8)_25") (pintype "bidirectional"))
    )
    (net (code "16") (name "/GPIO2") (class "Default")
      (node (ref "R19") (pin "1") (pinfunction "1_1") (pintype "passive"))
      (node (ref "R19") (pin "2") (pinfunction "2_2") (pintype "passive"))
      (node (ref "R24") (pin "1") (pinfunction "1_1") (pintype "passive"))
      (node (ref "U1") (pin "11") (pinfunction "GPIO2_11") (pintype "passive"))
      (node (ref "U3") (pin "27") (pinfunction "PD7_(T0/OC4D/ADC10)_27") (pintype "bidirectional"))
    )
    (net (code "17") (name "/GPIO3") (class "Default")
      (node (ref "R21") (pin "1") (pinfunction "1_1") (pintype "passive"))
      (node (ref "R21") (pin "2") (pinfunction "2_2") (pintype "passive"))
      (node (ref "R26") (pin "1") (pinfunction "1_1") (pintype "passive"))
      (node (ref "U1") (pin "9") (pinfunction "GPIO3_9") (pintype "passive"))
      (node (ref "U3") (pin "29") (pinfunction "PB5_(PCINT5/OC1A/~{OC4B}/ADC12)_29") (pintype "bidirectional"))
    )
    (net (code "18") (name "/GPIO4") (class "Default")
      (node (ref "R22") (pin "1") (pinfunction "1_1") (pintype "passive"))
      (node (ref "R22") (pin "2") (pinfunction "2_2") (pintype "passive"))
      (node (ref "R27") (pin "1") (pinfunction "1_1") (pintype "passive"))
      (node (ref "U1") (pin "10") (pinfunction "GPIO4_10") (pintype "passive"))
      (node (ref "U3") (pin "28") (pinfunction "PB4_(PCINT4/ADC11)_28") (pintype "bidirectional"))
    )
    (net (code "19") (name "/GPIO5") (class "Default")
      (node (ref "R10") (pin "1") (pinfunction "1_1") (pintype "passive"))
      (node (ref "R10") (pin "2") (pinfunction "2_2") (pintype "passive"))
      (node (ref "R29") (pin "1") (pinfunction "1_1") (pintype "passive"))
      (node (ref "U1") (pin "4") (pinfunction "GPIO5_4") (pintype "passive"))
      (node (ref "U3") (pin "30") (pinfunction "PB6_(PCINT6/OC1B/OC4B/ADC13)_30") (pintype "bidirectional"))
    )
    (net (code "20") (name "/GPIO7") (class "Default")
      (node (ref "R30") (pin "1") (pinfunction "1_1") (pintype "passive"))
      (node (ref "R7") (pin "1") (pinfunction "1_1") (pintype "passive"))
      (node (ref "R7") (pin "2") (pinfunction "2_2") (pintype "passive"))
      (node (ref "U1") (pin "18") (pinfunction "GPIO7_18") (pintype "passive"))
      (node (ref "U3") (pin "32") (pinfunction "PC7_(ICP3/CLK0/~{OC4A})_32") (pintype "bidirectional"))
    )
    (net (code "21") (name "/Led_B") (class "Default")
      (node (ref "R28") (pin "1") (pinfunction "1_1") (pintype "passive"))
      (node (ref "U3") (pin "41") (pinfunction "PF0_(ADC0)_41") (pintype "bidirectional"))
    )
    (net (code "22") (name "/Led_G") (class "Default")
      (node (ref "R25") (pin "1") (pinfunction "1_1") (pintype "passive"))
      (node (ref "U3") (pin "40") (pinfunction "PF1_(ADC1)_40") (pintype "bidirectional"))
    )
    (net (code "23") (name "/Led_R") (class "Default")
      (node (ref "R23") (pin "1") (pinfunction "1_1") (pintype "passive"))
      (node (ref "U3") (pin "39") (pinfunction "PF4_(ADC4/TCK)_39") (pintype "bidirectional"))
    )
    (net (code "24") (name "/MISO") (class "Default")
      (node (ref "P1") (pin "1") (pinfunction "1_1") (pintype "passive"))
      (node (ref "U3") (pin "11") (pinfunction "PB3_(PDO/PCINT3/MISO)_11") (pintype "passive"))
    )
    (net (code "25") (name "/MODE") (class "Default")
      (node (ref "R20") (pin "2") (pinfunction "2_2") (pintype "passive"))
      (node (ref "U1") (pin "5") (pinfunction "I2C_MODE_5") (pintype "passive"))
    )
    (net (code "26") (name "/MOSI") (class "Default")
      (node (ref "P1") (pin "4") (pinfunction "4_4") (pintype "passive"))
      (node (ref "U3") (pin "10") (pinfunction "PB2_(PDI/PCINT2/MOSI)_10") (pintype "bidirectional"))
    )
    (net (code "27") (name "/NTC") (class "Default")
      (node (ref "C1") (pin "1") (pinfunction "1_1") (pintype "passive"))
      (node (ref "R2") (pin "1") (pinfunction "1_1") (pintype "passive"))
      (node (ref "R3") (pin "2") (pinfunction "2_2") (pintype "passive"))
      (node (ref "U1") (pin "13") (pinfunction "NTC_13") (pintype "passive"))
    )
    (net (code "28") (name "/NTC2") (class "Default")
      (node (ref "R42") (pin "1") (pinfunction "1_1") (pintype "passive"))
      (node (ref "R43") (pin "2") (pinfunction "2_2") (pintype "passive"))
      (node (ref "U3") (pin "26") (pinfunction "PD6_(T1/~{OC4D}/ADC9)_26") (pintype "bidirectional"))
    )
    (net (code "29") (name "/RESET") (class "Default")
      (node (ref "P1") (pin "5") (pinfunction "5_5") (pintype "passive"))
      (node (ref "R33") (pin "1") (pinfunction "1_1") (pintype "passive"))
      (node (ref "U3") (pin "13") (pinfunction "~{RESET}_13") (pintype "passive"))
    )
    (net (code "30") (name "/SCK") (class "Default")
      (node (ref "P1") (pin "3") (pinfunction "3_3") (pintype "passive"))
      (node (ref "U3") (pin "9") (pinfunction "PB1_(PCINT1/SCLK)_9") (pintype "bidirectional"))
    )
    (net (code "31") (name "/SCL") (class "Default")
      (node (ref "U1") (pin "2") (pinfunction "SCL_2") (pintype "passive"))
      (node (ref "U3") (pin "18") (pinfunction "PD0_(OC0B/SCL/INT0)_18") (pintype "bidirectional"))
    )
    (net (code "32") (name "/SDA") (class "Default")
      (node (ref "U1") (pin "1") (pinfunction "SDA_1") (pintype "passive"))
      (node (ref "U3") (pin "19") (pinfunction "PD1_(SDA/INT1)_19") (pintype "input"))
    )
    (net (code "33") (name "/VMsense") (class "Default")
      (node (ref "R36") (pin "1") (pinfunction "1_1") (pintype "passive"))
      (node (ref "R37") (pin "2") (pinfunction "2_2") (pintype "passive"))
      (node (ref "U3") (pin "36") (pinfunction "PF7_(ADC7/TDI)_36") (pintype "bidirectional"))
    )
    (net (code "34") (name "/VSEL1") (class "Default")
      (node (ref "R12") (pin "1") (pinfunction "1_1") (pintype "passive"))
      (node (ref "R16") (pin "1") (pinfunction "1_1") (pintype "passive"))
      (node (ref "R16") (pin "2") (pinfunction "2_2") (pintype "passive"))
      (node (ref "U1") (pin "3") (pinfunction "GPIO1_3") (pintype "passive"))
      (node (ref "U2") (pin "4") (pinfunction "VSEL1_4") (pintype "passive"))
    )
    (net (code "35") (name "/VSEL2") (class "Default")
      (node (ref "R11") (pin "1") (pinfunction "1_1") (pintype "passive"))
      (node (ref "R14") (pin "1") (pinfunction "1_1") (pintype "passive"))
      (node (ref "R14") (pin "2") (pinfunction "2_2") (pintype "passive"))
      (node (ref "U1") (pin "12") (pinfunction "GPIO6_12") (pintype "passive"))
      (node (ref "U2") (pin "5") (pinfunction "VSEL2_5") (pintype "passive"))
    )
    (net (code "36") (name "/XTAL1") (class "Default")
      (node (ref "C19") (pin "2") (pinfunction "2_2") (pintype "passive"))
      (node (ref "U3") (pin "17") (pinfunction "XTAL1_17") (pintype "passive"))
      (node (ref "Y1") (pin "3") (pinfunction "3_3") (pintype "passive"))
    )
    (net (code "37") (name "/XTAL2") (class "Default")
      (node (ref "C20") (pin "2") (pinfunction "2_2") (pintype "passive"))
      (node (ref "U3") (pin "16") (pinfunction "XTAL2_16") (pintype "passive"))
      (node (ref "Y1") (pin "1") (pinfunction "1_1") (pintype "passive"))
    )
    (net (code "38") (name "GND") (class "Default")
      (node (ref "C1") (pin "2") (pinfunction "2_2") (pintype "passive"))
      (node (ref "C10") (pin "2") (pinfunction "2_2") (pintype "passive"))
      (node (ref "C11") (pin "1") (pinfunction "1_1") (pintype "passive"))
      (node (ref "C14") (pin "2") (pinfunction "2_2") (pintype "passive"))
      (node (ref "C15") (pin "1") (pinfunction "1_1") (pintype "passive"))
      (node (ref "C16") (pin "2") (pinfunction "2_2") (pintype "passive"))
      (node (ref "C17") (pin "2") (pinfunction "2_2") (pintype "passive"))
      (node (ref "C18") (pin "2") (pinfunction "2_2") (pintype "passive"))
      (node (ref "C19") (pin "1") (pinfunction "1_1") (pintype "passive"))
      (node (ref "C2") (pin "1") (pinfunction "C_1") (pintype "passive"))
      (node (ref "C20") (pin "1") (pinfunction "1_1") (pintype "passive"))
      (node (ref "C21") (pin "2") (pinfunction "2_2") (pintype "passive"))
      (node (ref "C22") (pin "2") (pinfunction "2_2") (pintype "passive"))
      (node (ref "C23") (pin "2") (pinfunction "2_2") (pintype "passive"))
      (node (ref "C24") (pin "2") (pinfunction "2_2") (pintype "passive"))
      (node (ref "C25") (pin "2") (pinfunction "2_2") (pintype "passive"))
      (node (ref "C26") (pin "2") (pinfunction "2_2") (pintype "passive"))
      (node (ref "C27") (pin "2") (pinfunction "2_2") (pintype "passive"))
      (node (ref "C28") (pin "1") (pinfunction "1_1") (pintype "passive"))
      (node (ref "C29") (pin "1") (pinfunction "1_1") (pintype "passive"))
      (node (ref "C3") (pin "1") (pinfunction "C_1") (pintype "passive"))
      (node (ref "C4") (pin "2") (pinfunction "2_2") (pintype "passive"))
      (node (ref "C5") (pin "2") (pinfunction "2_2") (pintype "passive"))
      (node (ref "C6") (pin "1") (pinfunction "C_1") (pintype "passive"))
      (node (ref "C7") (pin "2") (pinfunction "2_2") (pintype "passive"))
      (node (ref "C8") (pin "2") (pinfunction "2_2") (pintype "passive"))
      (node (ref "C9") (pin "2") (pinfunction "2_2") (pintype "passive"))
      (node (ref "D1") (pin "1") (pinfunction "1_1") (pintype "passive"))
      (node (ref "D2") (pin "2") (pinfunction "2_2") (pintype "passive"))
      (node (ref "D3") (pin "2") (pinfunction "2_2") (pintype "passive"))
      (node (ref "D4") (pin "2") (pinfunction "2_2") (pintype "passive"))
      (node (ref "D5") (pin "1") (pinfunction "1_1") (pintype "passive"))
      (node (ref "DS1") (pin "2") (pinfunction "K_2") (pintype "passive"))
      (node (ref "DS2") (pin "2") (pinfunction "K_2") (pintype "passive"))
      (node (ref "J1") (pin "2") (pinfunction "-_2") (pintype "passive"))
      (node (ref "J1") (pin "MH1") (pinfunction "3_MH1") (pintype "passive"))
      (node (ref "J1") (pin "MH2") (pinfunction "4_MH2") (pintype "passive"))
      (node (ref "J3") (pin "A1") (pinfunction "GND_A1") (pintype "passive"))
      (node (ref "J3") (pin "A12") (pinfunction "GND_A12") (pintype "passive"))
      (node (ref "J3") (pin "B1") (pinfunction "GND_B1") (pintype "passive"))
      (node (ref "J3") (pin "B12") (pinfunction "GND_B12") (pintype "passive"))
      (node (ref "J3") (pin "MP") (pinfunction "MP_MP") (pintype "passive"))
      (node (ref "J4") (pin "3") (pinfunction "3_3") (pintype "passive"))
      (node (ref "J4") (pin "5") (pinfunction "MNT_1_5") (pintype "passive"))
      (node (ref "J4") (pin "6") (pinfunction "MNT_2_6") (pintype "passive"))
      (node (ref "J5") (pin "A1") (pinfunction "GND_A1") (pintype "passive"))
      (node (ref "J5") (pin "A12") (pinfunction "GND_A12") (pintype "passive"))
      (node (ref "J5") (pin "B1") (pinfunction "GND_B1") (pintype "passive"))
      (node (ref "J5") (pin "B12") (pinfunction "GND_B12") (pintype "passive"))
      (node (ref "J5") (pin "MP") (pinfunction "MP_MP") (pintype "passive"))
      (node (ref "J6") (pin "3") (pinfunction "3_3") (pintype "passive"))
      (node (ref "P1") (pin "6") (pinfunction "6_6") (pintype "passive"))
      (node (ref "R13") (pin "1") (pinfunction "1_1") (pintype "passive"))
      (node (ref "R17") (pin "1") (pinfunction "1_1") (pintype "passive"))
      (node (ref "R18") (pin "1") (pinfunction "1_1") (pintype "passive"))
      (node (ref "R3") (pin "1") (pinfunction "1_1") (pintype "passive"))
      (node (ref "R34") (pin "1") (pinfunction "1_1") (pintype "passive"))
      (node (ref "R35") (pin "1") (pinfunction "1_1") (pintype "passive"))
      (node (ref "R37") (pin "1") (pinfunction "1_1") (pintype "passive"))
      (node (ref "R43") (pin "1") (pinfunction "1_1") (pintype "passive"))
      (node (ref "U1") (pin "21") (pinfunction "EPAD_21") (pintype "passive"))
      (node (ref "U1") (pin "8") (pinfunction "GND_8") (pintype "passive"))
      (node (ref "U2") (pin "2") (pinfunction "PGND_2") (pintype "passive"))
      (node (ref "U2") (pin "7") (pinfunction "AGND_7") (pintype "passive"))
      (node (ref "U3") (pin "15") (pinfunction "GND_15") (pintype "power_in"))
      (node (ref "U3") (pin "23") (pinfunction "GND_23") (pintype "power_in"))
      (node (ref "U3") (pin "35") (pinfunction "GND_35") (pintype "power_in"))
      (node (ref "U3") (pin "43") (pinfunction "GND_43") (pintype "power_in"))
      (node (ref "U3") (pin "45") (pinfunction "DAP_45") (pintype "power_in"))
      (node (ref "U3") (pin "5") (pinfunction "UGnd_5") (pintype "power_in"))
      (node (ref "U4") (pin "2") (pinfunction "GND_2") (pintype "power_in"))
      (node (ref "U5") (pin "2") (pinfunction "GND_2") (pintype "power_in"))
      (node (ref "Y1") (pin "2") (pinfunction "GND_2") (pintype "power_in"))
      (node (ref "Y1") (pin "4") (pinfunction "GND_4") (pintype "power_in"))
    )
    (net (code "39") (name "Net-(D2-Pad1)") (class "Default")
      (node (ref "D2") (pin "1") (pinfunction "1_1") (pintype "passive"))
      (node (ref "R4") (pin "2") (pinfunction "2_2") (pintype "passive"))
    )
    (net (code "40") (name "Net-(D2-Pad3)") (class "Default")
      (node (ref "D2") (pin "3") (pinfunction "3_3") (pintype "passive"))
      (node (ref "R6") (pin "2") (pinfunction "2_2") (pintype "passive"))
    )
    (net (code "41") (name "Net-(DS1-A)") (class "Default")
      (node (ref "DS1") (pin "1") (pinfunction "A_1") (pintype "passive"))
      (node (ref "R1") (pin "1") (pinfunction "1_1") (pintype "passive"))
    )
    (net (code "42") (name "Net-(DS2-A)") (class "Default")
      (node (ref "DS2") (pin "1") (pinfunction "A_1") (pintype "passive"))
      (node (ref "R8") (pin "1") (pinfunction "1_1") (pintype "passive"))
      (node (ref "U2") (pin "13") (pinfunction "PG_13") (pintype "passive"))
    )
    (net (code "43") (name "Net-(DS3-A)") (class "Default")
      (node (ref "DS3") (pin "1") (pinfunction "A_1") (pintype "passive"))
      (node (ref "R39") (pin "2") (pinfunction "2_2") (pintype "passive"))
    )
    (net (code "44") (name "Net-(DS3-K)") (class "Default")
      (node (ref "DS3") (pin "2") (pinfunction "K_2") (pintype "passive"))
      (node (ref "U4") (pin "5") (pinfunction "ST_5") (pintype "output"))
    )
    (net (code "45") (name "Net-(DS4-A)") (class "Default")
      (node (ref "DS4") (pin "1") (pinfunction "A_1") (pintype "passive"))
      (node (ref "R40") (pin "2") (pinfunction "2_2") (pintype "passive"))
    )
    (net (code "46") (name "Net-(DS4-K)") (class "Default")
      (node (ref "DS4") (pin "2") (pinfunction "K_2") (pintype "passive"))
      (node (ref "U5") (pin "5") (pinfunction "ST_5") (pintype "output"))
    )
    (net (code "47") (name "Net-(J2-Pad2)") (class "Default")
      (node (ref "J2") (pin "2") (pinfunction "2_2") (pintype "passive"))
      (node (ref "R23") (pin "2") (pinfunction "2_2") (pintype "passive"))
    )
    (net (code "48") (name "Net-(J2-Pad3)") (class "Default")
      (node (ref "J2") (pin "3") (pinfunction "3_3") (pintype "passive"))
      (node (ref "R25") (pin "2") (pinfunction "2_2") (pintype "passive"))
    )
    (net (code "49") (name "Net-(J2-Pad4)") (class "Default")
      (node (ref "J2") (pin "4") (pinfunction "4_4") (pintype "passive"))
      (node (ref "R28") (pin "2") (pinfunction "2_2") (pintype "passive"))
    )
    (net (code "50") (name "Net-(J5-CC1)") (class "Default")
      (node (ref "J5") (pin "A5") (pinfunction "CC1_A5") (pintype "passive"))
      (node (ref "R34") (pin "2") (pinfunction "2_2") (pintype "passive"))
    )
    (net (code "51") (name "Net-(J5-CC2)") (class "Default")
      (node (ref "J5") (pin "B5") (pinfunction "CC2_B5") (pintype "passive"))
      (node (ref "R35") (pin "2") (pinfunction "2_2") (pintype "passive"))
    )
    (net (code "52") (name "Net-(U1-CC1)") (class "Default")
      (node (ref "C9") (pin "1") (pinfunction "1_1") (pintype "passive"))
      (node (ref "R4") (pin "1") (pinfunction "1_1") (pintype "passive"))
      (node (ref "U1") (pin "15") (pinfunction "CC1_15") (pintype "passive"))
    )
    (net (code "53") (name "Net-(U1-CC2)") (class "Default")
      (node (ref "C11") (pin "2") (pinfunction "2_2") (pintype "passive"))
      (node (ref "R6") (pin "1") (pinfunction "1_1") (pintype "passive"))
      (node (ref "U1") (pin "14") (pinfunction "CC2_14") (pintype "passive"))
    )
    (net (code "54") (name "Net-(U1-DM)") (class "Default")
      (node (ref "D3") (pin "1") (pinfunction "1_1") (pintype "passive"))
      (node (ref "U1") (pin "17") (pinfunction "DM_17") (pintype "passive"))
    )
    (net (code "55") (name "Net-(U1-DP)") (class "Default")
      (node (ref "D3") (pin "3") (pinfunction "3_3") (pintype "passive"))
      (node (ref "U1") (pin "16") (pinfunction "DP_16") (pintype "passive"))
    )
    (net (code "56") (name "Net-(U1-VDD)") (class "Default")
      (node (ref "C18") (pin "1") (pinfunction "1_1") (pintype "passive"))
      (node (ref "U1") (pin "6") (pinfunction "VDD_6") (pintype "passive"))
    )
    (net (code "57") (name "Net-(U1-VDRV)") (class "Default")
      (node (ref "TP1") (pin "1") (pinfunction "1_1") (pintype "passive"))
      (node (ref "U1") (pin "19") (pinfunction "VDRV_19") (pintype "passive"))
    )
    (net (code "58") (name "Net-(U2-BST)") (class "Default")
      (node (ref "C12") (pin "2") (pinfunction "2_2") (pintype "passive"))
      (node (ref "U2") (pin "9") (pinfunction "BST_9") (pintype "passive"))
    )
    (net (code "59") (name "Net-(U2-FB)") (class "Default")
      (node (ref "C13") (pin "2") (pinfunction "2_2") (pintype "passive"))
      (node (ref "R13") (pin "2") (pinfunction "2_2") (pintype "passive"))
      (node (ref "R9") (pin "1") (pinfunction "1_1") (pintype "passive"))
      (node (ref "U2") (pin "6") (pinfunction "FB_6") (pintype "passive"))
    )
    (net (code "60") (name "Net-(U2-ILIM)") (class "Default")
      (node (ref "R17") (pin "2") (pinfunction "2_2") (pintype "passive"))
      (node (ref "U2") (pin "12") (pinfunction "ILIM_12") (pintype "passive"))
    )
    (net (code "61") (name "Net-(U2-MODE)") (class "Default")
      (node (ref "R15") (pin "1") (pinfunction "1_1") (pintype "passive"))
      (node (ref "R18") (pin "2") (pinfunction "2_2") (pintype "passive"))
      (node (ref "U2") (pin "10") (pinfunction "MODE_10") (pintype "passive"))
    )
    (net (code "62") (name "Net-(U2-SW)") (class "Default")
      (node (ref "C12") (pin "1") (pinfunction "1_1") (pintype "passive"))
      (node (ref "L1") (pin "1") (pinfunction "1_1") (pintype "passive"))
      (node (ref "U2") (pin "8") (pinfunction "SW_8") (pintype "passive"))
    )
    (net (code "63") (name "Net-(U3-D+)") (class "Default")
      (node (ref "R32") (pin "2") (pinfunction "2_2") (pintype "passive"))
      (node (ref "U3") (pin "4") (pinfunction "D+_4") (pintype "bidirectional"))
    )
    (net (code "64") (name "Net-(U3-D-)") (class "Default")
      (node (ref "R31") (pin "2") (pinfunction "2_2") (pintype "passive"))
      (node (ref "U3") (pin "3") (pinfunction "D-_3") (pintype "bidirectional"))
    )
    (net (code "65") (name "Net-(U3-PF6_(ADC6{slash}TDO)") (class "Default")
      (node (ref "R38") (pin "2") (pinfunction "2_2") (pintype "passive"))
      (node (ref "U3") (pin "37") (pinfunction "PF6_(ADC6/TDO_37") (pintype "bidirectional"))
    )
    (net (code "66") (name "Net-(U3-UCap)") (class "Default")
      (node (ref "C21") (pin "1") (pinfunction "1_1") (pintype "passive"))
      (node (ref "U3") (pin "6") (pinfunction "UCap_6") (pintype "passive"))
    )
    (net (code "67") (name "VBUS") (class "Default")
      (node (ref "C10") (pin "1") (pinfunction "1_1") (pintype "passive"))
      (node (ref "C13") (pin "1") (pinfunction "1_1") (pintype "passive"))
      (node (ref "C2") (pin "2") (pinfunction "A_2") (pintype "passive"))
      (node (ref "C3") (pin "2") (pinfunction "A_2") (pintype "passive"))
      (node (ref "C4") (pin "1") (pinfunction "1_1") (pintype "passive"))
      (node (ref "C5") (pin "1") (pinfunction "1_1") (pintype "passive"))
      (node (ref "D5") (pin "2") (pinfunction "2_2") (pintype "passive"))
      (node (ref "J3") (pin "A4") (pinfunction "VBUS_A4") (pintype "passive"))
      (node (ref "J3") (pin "A9") (pinfunction "VBUS_A9") (pintype "passive"))
      (node (ref "J3") (pin "B4") (pinfunction "VBUS_B4") (pintype "passive"))
      (node (ref "J3") (pin "B9") (pinfunction "VBUS_B9") (pintype "passive"))
      (node (ref "L1") (pin "2") (pinfunction "2_2") (pintype "passive"))
      (node (ref "R36") (pin "2") (pinfunction "2_2") (pintype "passive"))
      (node (ref "R9") (pin "2") (pinfunction "2_2") (pintype "passive"))
      (node (ref "U1") (pin "20") (pinfunction "VBUS_P_20") (pintype "passive"))
    )
    (net (code "68") (name "VM") (class "Default")
      (node (ref "C6") (pin "2") (pinfunction "A_2") (pintype "passive"))
      (node (ref "C7") (pin "1") (pinfunction "1_1") (pintype "passive"))
      (node (ref "C8") (pin "1") (pinfunction "1_1") (pintype "passive"))
      (node (ref "D1") (pin "2") (pinfunction "2_2") (pintype "passive"))
      (node (ref "J1") (pin "1") (pinfunction "+_1") (pintype "passive"))
      (node (ref "R1") (pin "2") (pinfunction "2_2") (pintype "passive"))
      (node (ref "R39") (pin "1") (pinfunction "1_1") (pintype "passive"))
      (node (ref "R40") (pin "1") (pinfunction "1_1") (pintype "passive"))
      (node (ref "R5") (pin "2") (pinfunction "2_2") (pintype "passive"))
      (node (ref "U2") (pin "1") (pinfunction "IN_1") (pintype "passive"))
    )
    (net (code "69") (name "unconnected-(J3-NC-PadA8)") (class "Default")
      (node (ref "J3") (pin "A8") (pinfunction "NC_A8") (pintype "passive+no_connect"))
    )
    (net (code "70") (name "unconnected-(J3-NC-PadB8)") (class "Default")
      (node (ref "J3") (pin "B8") (pinfunction "NC_B8") (pintype "passive+no_connect"))
    )
    (net (code "71") (name "unconnected-(J5-NC-PadA8)") (class "Default")
      (node (ref "J5") (pin "A8") (pinfunction "NC_A8") (pintype "passive+no_connect"))
    )
    (net (code "72") (name "unconnected-(J5-NC-PadB8)") (class "Default")
      (node (ref "J5") (pin "B8") (pinfunction "NC_B8") (pintype "passive+no_connect"))
    )
    (net (code "73") (name "unconnected-(U3-PB0_(SS{slash}PCINT0)-Pad8)") (class "Default")
      (node (ref "U3") (pin "8") (pinfunction "PB0_(SS/PCINT0)_8") (pintype "bidirectional"))
    )
    (net (code "74") (name "unconnected-(U3-PB7_(PCINT7{slash}OC0A{slash}OC1C{slash}~{RTS})-Pad12)") (class "Default")
      (node (ref "U3") (pin "12") (pinfunction "PB7_(PCINT7/OC0A/OC1C/~{RTS})_12") (pintype "passive"))
    )
    (net (code "75") (name "unconnected-(U3-PD2_(RXD1{slash}INT2)-Pad20)") (class "Default")
      (node (ref "U3") (pin "20") (pinfunction "PD2_(RXD1/INT2)_20") (pintype "bidirectional"))
    )
    (net (code "76") (name "unconnected-(U3-PD3_(TXD1{slash}INT3)-Pad21)") (class "Default")
      (node (ref "U3") (pin "21") (pinfunction "PD3_(TXD1/INT3)_21") (pintype "bidirectional"))
    )
    (net (code "77") (name "unconnected-(U3-PD5_(XCK1{slash}~{CTS})-Pad22)") (class "Default")
      (node (ref "U3") (pin "22") (pinfunction "PD5_(XCK1/~{CTS})_22") (pintype "bidirectional"))
    )
    (net (code "78") (name "unconnected-(U3-PE6_(INT.6{slash}AIN0)-Pad1)") (class "Default")
      (node (ref "U3") (pin "1") (pinfunction "PE6_(INT.6/AIN0)_1") (pintype "bidirectional"))
    )
    (net (code "79") (name "unconnected-(U4-NC-Pad4)") (class "Default")
      (node (ref "U4") (pin "4") (pinfunction "NC_4") (pintype "passive+no_connect"))
    )
    (net (code "80") (name "unconnected-(U5-NC-Pad4)") (class "Default")
      (node (ref "U5") (pin "4") (pinfunction "NC_4") (pintype "passive+no_connect"))
    )
  )
)
